# Display_port.net
KiCad netlist of a schematic drawn in Altium Designer
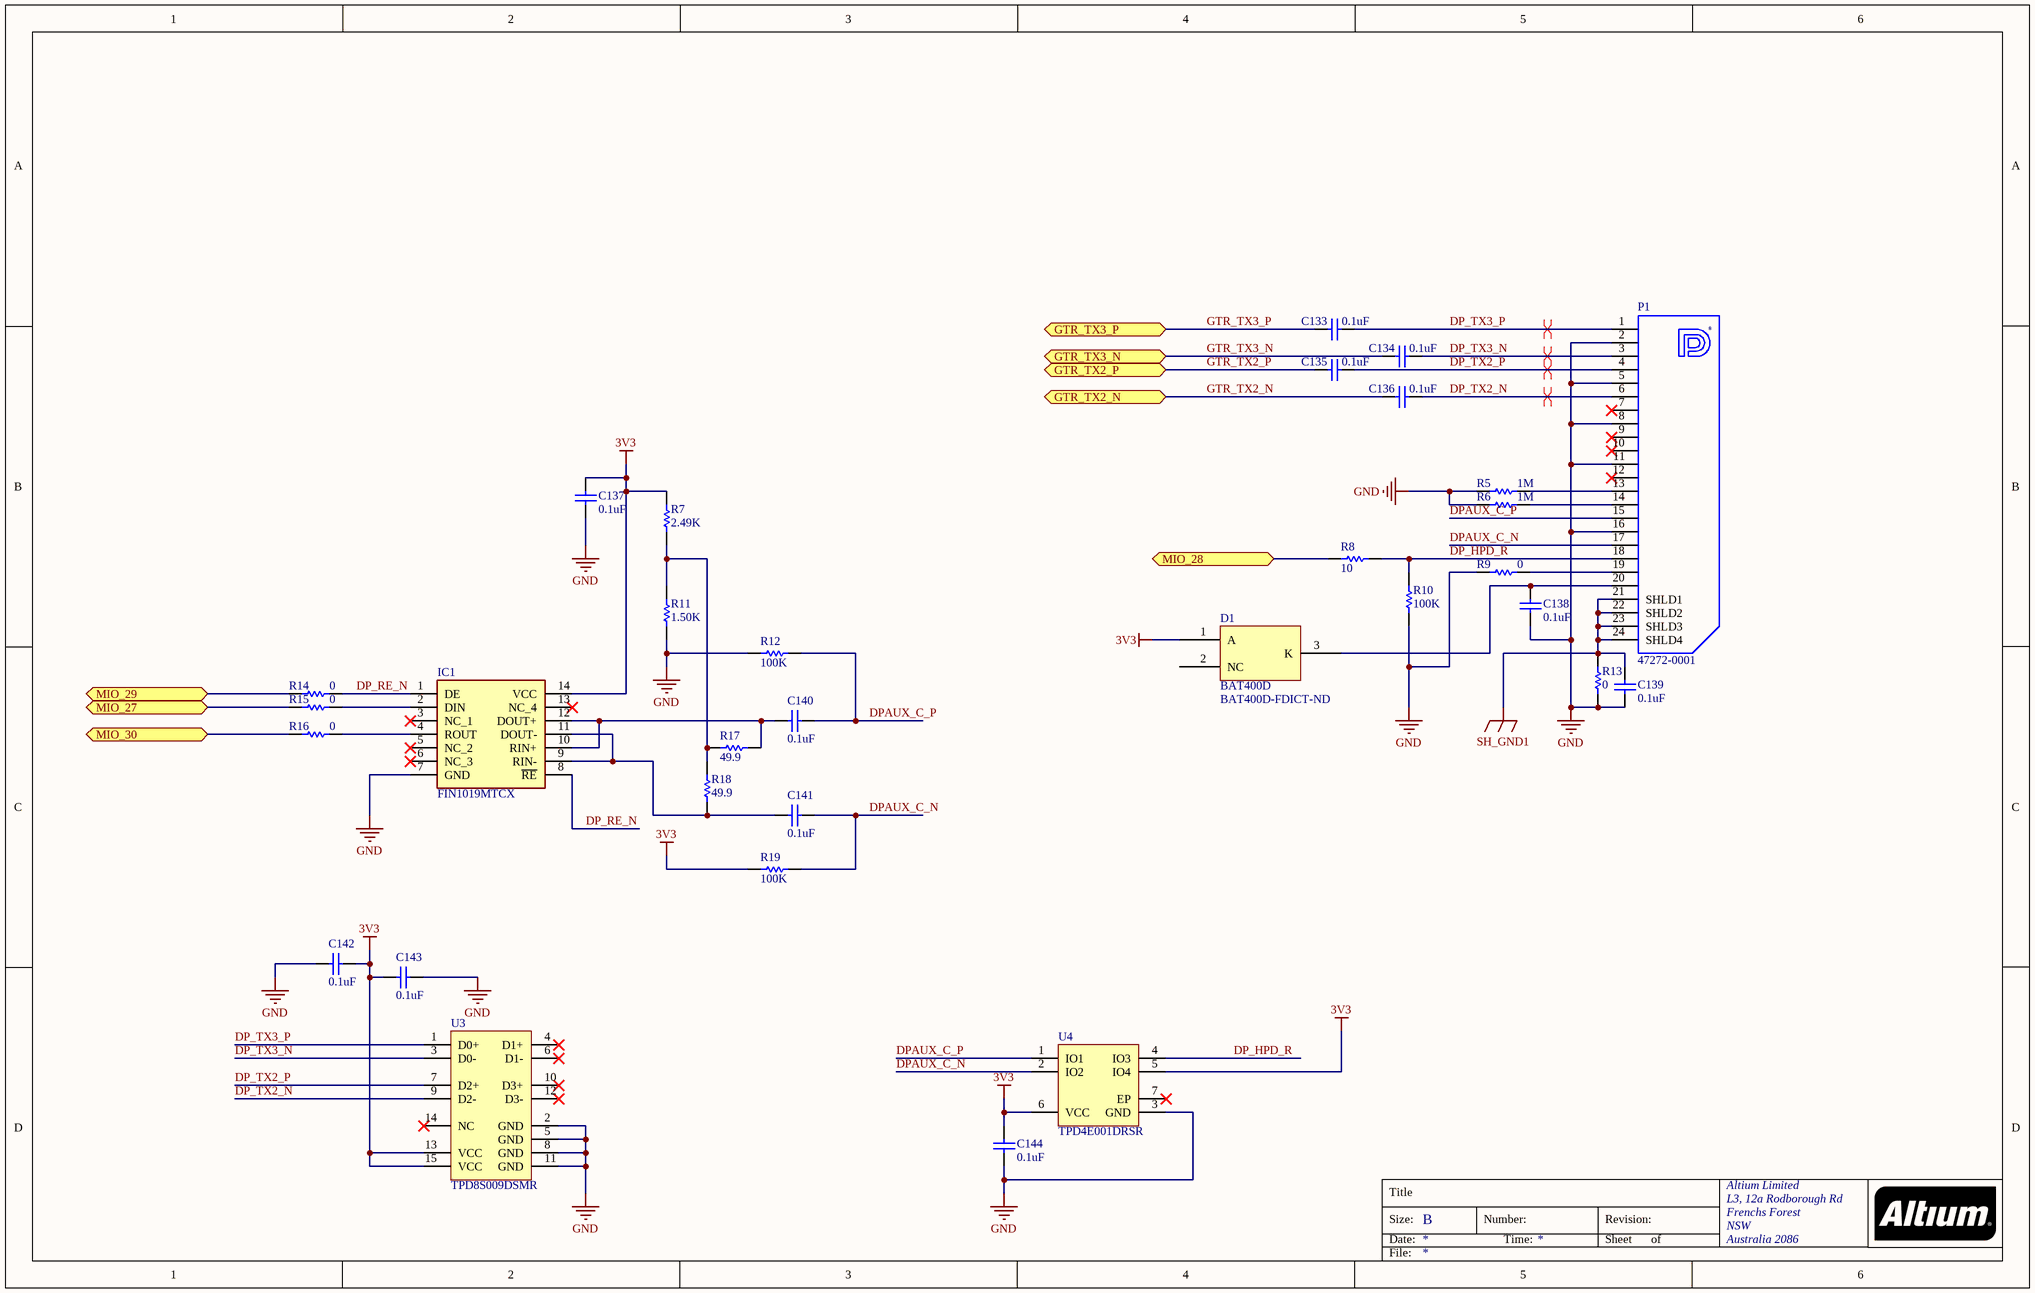
[diagram p0: Display_port.SchDoc]

(export (version "E")
  (design (tool "Eeschema 10.0.6"))
  (components
    (comp (ref "C133")
      (value "0.1uF")
      (footprint "CAPC0201(0603)33_N")
      (libsource (lib "my_schsymbols") (part "CAP_0201"))
    )
    (comp (ref "C134")
      (value "0.1uF")
      (footprint "CAPC0201(0603)33_N")
      (libsource (lib "my_schsymbols") (part "CAP_0201"))
    )
    (comp (ref "C135")
      (value "0.1uF")
      (footprint "CAPC0201(0603)33_N")
      (libsource (lib "my_schsymbols") (part "CAP_0201"))
    )
    (comp (ref "C136")
      (value "0.1uF")
      (footprint "CAPC0201(0603)33_N")
      (libsource (lib "my_schsymbols") (part "CAP_0201"))
    )
    (comp (ref "C137")
      (value "0.1uF")
      (footprint "CAPC0201(0603)33_N")
      (libsource (lib "my_schsymbols") (part "CAP_0201"))
    )
    (comp (ref "C138")
      (value "0.1uF")
      (footprint "CAPC0201(0603)33_N")
      (libsource (lib "my_schsymbols") (part "CAP_0201"))
    )
    (comp (ref "C139")
      (value "0.1uF")
      (footprint "CAPC0201(0603)33_N")
      (libsource (lib "my_schsymbols") (part "CAP_0201"))
    )
    (comp (ref "C140")
      (value "0.1uF")
      (footprint "CAPC0201(0603)33_N")
      (libsource (lib "my_schsymbols") (part "CAP_0201"))
    )
    (comp (ref "C141")
      (value "0.1uF")
      (footprint "CAPC0201(0603)33_N")
      (libsource (lib "my_schsymbols") (part "CAP_0201"))
    )
    (comp (ref "C142")
      (value "0.1uF")
      (footprint "CAPC0201(0603)33_N")
      (libsource (lib "my_schsymbols") (part "CAP_0201"))
    )
    (comp (ref "C143")
      (value "0.1uF")
      (footprint "CAPC0201(0603)33_N")
      (libsource (lib "my_schsymbols") (part "CAP_0201"))
    )
    (comp (ref "C144")
      (value "0.1uF")
      (footprint "CAPC0201(0603)33_N")
      (libsource (lib "my_schsymbols") (part "CAP_0201"))
    )
    (comp (ref "D1")
      (value "BAT400D")
      (footprint "SOT95P236X110-3N")
      (fields (field (name "SUPPLIER PART NUMBER 1") "BAT400D-FDICT-ND"))
      (libsource (lib "CGRA_schlib") (part "BAT400D"))
    )
    (comp (ref "IC1")
      (value "FIN1019MTCX")
      (footprint "SamacSys:SOP65P640X120-14N")
      (description "Integrated Circuit")
      (fields
        (field (name "MOUSER PART NUMBER") "512-FIN1019MTCX")
        (field (name "RS PART NUMBER") "8070805P")
      )
      (libsource (lib "*") (part "FIN1019MTCX"))
    )
    (comp (ref "P1")
      (value "47272-0001")
      (footprint "MOLX-47272-0001_V")
      (fields (field (name "MANUFACTURER") "Molex"))
      (libsource (lib "Altium Content Vault") (part "CN-1P-4M-DP20"))
    )
    (comp (ref "R5")
      (value "1M")
      (footprint "RESC0402(1005)_N")
      (libsource (lib "my_schsymbols") (part "RES_0402"))
    )
    (comp (ref "R6")
      (value "1M")
      (footprint "RESC0402(1005)_N")
      (libsource (lib "my_schsymbols") (part "RES_0402"))
    )
    (comp (ref "R7")
      (value "2.49K")
      (footprint "RESC0402(1005)_N")
      (libsource (lib "my_schsymbols") (part "RES_0402"))
    )
    (comp (ref "R8")
      (value "10")
      (footprint "RESC0402(1005)_N")
      (libsource (lib "my_schsymbols") (part "RES_0402"))
    )
    (comp (ref "R9")
      (value "0")
      (footprint "RESC0402(1005)_N")
      (libsource (lib "my_schsymbols") (part "RES_0402"))
    )
    (comp (ref "R10")
      (value "100K")
      (footprint "RESC0402(1005)_N")
      (libsource (lib "my_schsymbols") (part "RES_0402"))
    )
    (comp (ref "R11")
      (value "1.50K")
      (footprint "RESC0402(1005)_N")
      (libsource (lib "my_schsymbols") (part "RES_0402"))
    )
    (comp (ref "R12")
      (value "100K")
      (footprint "RESC0402(1005)_N")
      (libsource (lib "my_schsymbols") (part "RES_0402"))
    )
    (comp (ref "R13")
      (value "0")
      (footprint "RESC0402(1005)_N")
      (libsource (lib "my_schsymbols") (part "RES_0402"))
    )
    (comp (ref "R14")
      (value "0")
      (footprint "RESC0402(1005)_N")
      (libsource (lib "my_schsymbols") (part "RES_0402"))
    )
    (comp (ref "R15")
      (value "0")
      (footprint "RESC0402(1005)_N")
      (libsource (lib "my_schsymbols") (part "RES_0402"))
    )
    (comp (ref "R16")
      (value "0")
      (footprint "RESC0402(1005)_N")
      (libsource (lib "my_schsymbols") (part "RES_0402"))
    )
    (comp (ref "R17")
      (value "49.9")
      (footprint "RESC0402(1005)_N")
      (libsource (lib "my_schsymbols") (part "RES_0402"))
    )
    (comp (ref "R18")
      (value "49.9")
      (footprint "RESC0402(1005)_N")
      (libsource (lib "my_schsymbols") (part "RES_0402"))
    )
    (comp (ref "R19")
      (value "100K")
      (footprint "RESC0402(1005)_N")
      (libsource (lib "my_schsymbols") (part "RES_0402"))
    )
    (comp (ref "U3")
      (value "TPD8S009DSMR")
      (footprint "DSM0015A_V")
      (description "ESD Solution for HDMI / DisplayPort, 8 Channels, -40 to +85 degC, 15-pin SON (DSM)")
      (fields (field (name "MANUFACTURER") "Texas Instruments"))
      (libsource (lib "Altium Content Vault") (part "TI-TPD8S009-SON_DSM-15"))
    )
    (comp (ref "U4")
      (value "TPD4E001DRSR")
      (footprint "DRS0006A_V")
      (fields (field (name "MANUFACTURER") "Texas Instruments"))
      (libsource (lib "Altium Content Vault") (part "TI-TPD4E001-SON_DRS-6"))
    )
  )
  (nets
    (net (code "1") (name "/DPAUX_C_N") (class "Default")
      (node (ref "C141") (pin "2") (pinfunction "2_2") (pintype "passive"))
      (node (ref "P1") (pin "17") (pinfunction "17_17") (pintype "passive"))
      (node (ref "R19") (pin "1") (pinfunction "1_1") (pintype "passive"))
      (node (ref "U4") (pin "2") (pinfunction "IO2_2") (pintype "passive"))
    )
    (net (code "2") (name "/DPAUX_C_P") (class "Default")
      (node (ref "C140") (pin "2") (pinfunction "2_2") (pintype "passive"))
      (node (ref "P1") (pin "15") (pinfunction "15_15") (pintype "passive"))
      (node (ref "R12") (pin "1") (pinfunction "1_1") (pintype "passive"))
      (node (ref "U4") (pin "1") (pinfunction "IO1_1") (pintype "passive"))
    )
    (net (code "3") (name "/DP_HPD_R") (class "Default")
      (node (ref "P1") (pin "18") (pinfunction "18_18") (pintype "passive"))
      (node (ref "R10") (pin "2") (pinfunction "2_2") (pintype "passive"))
      (node (ref "R8") (pin "2") (pinfunction "2_2") (pintype "passive"))
      (node (ref "U4") (pin "4") (pinfunction "IO3_4") (pintype "passive"))
    )
    (net (code "4") (name "/DP_RE_N") (class "Default")
      (node (ref "IC1") (pin "1") (pinfunction "DE_1") (pintype "passive"))
      (node (ref "IC1") (pin "8") (pinfunction "~{RE}_8") (pintype "passive"))
      (node (ref "R14") (pin "1") (pinfunction "1_1") (pintype "passive"))
    )
    (net (code "5") (name "/DP_TX2_N") (class "Default")
      (node (ref "C136") (pin "2") (pinfunction "2_2") (pintype "passive"))
      (node (ref "P1") (pin "6") (pinfunction "6_6") (pintype "passive"))
      (node (ref "U3") (pin "9") (pinfunction "D2-_9") (pintype "passive"))
    )
    (net (code "6") (name "/DP_TX2_P") (class "Default")
      (node (ref "C135") (pin "2") (pinfunction "2_2") (pintype "passive"))
      (node (ref "P1") (pin "4") (pinfunction "4_4") (pintype "passive"))
      (node (ref "U3") (pin "7") (pinfunction "D2+_7") (pintype "passive"))
    )
    (net (code "7") (name "/DP_TX3_N") (class "Default")
      (node (ref "C134") (pin "2") (pinfunction "2_2") (pintype "passive"))
      (node (ref "P1") (pin "3") (pinfunction "3_3") (pintype "passive"))
      (node (ref "U3") (pin "3") (pinfunction "D0-_3") (pintype "passive"))
    )
    (net (code "8") (name "/DP_TX3_P") (class "Default")
      (node (ref "C133") (pin "2") (pinfunction "2_2") (pintype "passive"))
      (node (ref "P1") (pin "1") (pinfunction "1_1") (pintype "passive"))
      (node (ref "U3") (pin "1") (pinfunction "D0+_1") (pintype "passive"))
    )
    (net (code "9") (name "/GTR_TX2_N") (class "Default")
      (node (ref "C136") (pin "1") (pinfunction "1_1") (pintype "passive"))
    )
    (net (code "10") (name "/GTR_TX2_P") (class "Default")
      (node (ref "C135") (pin "1") (pinfunction "1_1") (pintype "passive"))
    )
    (net (code "11") (name "/GTR_TX3_N") (class "Default")
      (node (ref "C134") (pin "1") (pinfunction "1_1") (pintype "passive"))
    )
    (net (code "12") (name "/GTR_TX3_P") (class "Default")
      (node (ref "C133") (pin "1") (pinfunction "1_1") (pintype "passive"))
    )
    (net (code "13") (name "/MIO_27") (class "Default")
      (node (ref "R15") (pin "2") (pinfunction "2_2") (pintype "passive"))
    )
    (net (code "14") (name "/MIO_28") (class "Default")
      (node (ref "R8") (pin "1") (pinfunction "1_1") (pintype "passive"))
    )
    (net (code "15") (name "/MIO_29") (class "Default")
      (node (ref "R14") (pin "2") (pinfunction "2_2") (pintype "passive"))
    )
    (net (code "16") (name "/MIO_30") (class "Default")
      (node (ref "R16") (pin "2") (pinfunction "2_2") (pintype "passive"))
    )
    (net (code "17") (name "3V3") (class "Default")
      (node (ref "C137") (pin "2") (pinfunction "2_2") (pintype "passive"))
      (node (ref "C142") (pin "1") (pinfunction "1_1") (pintype "passive"))
      (node (ref "C143") (pin "2") (pinfunction "2_2") (pintype "passive"))
      (node (ref "C144") (pin "2") (pinfunction "2_2") (pintype "passive"))
      (node (ref "D1") (pin "1") (pinfunction "A_1") (pintype "passive"))
      (node (ref "IC1") (pin "14") (pinfunction "VCC_14") (pintype "passive"))
      (node (ref "R19") (pin "2") (pinfunction "2_2") (pintype "passive"))
      (node (ref "R7") (pin "2") (pinfunction "2_2") (pintype "passive"))
      (node (ref "U3") (pin "13") (pinfunction "VCC_13") (pintype "power_in"))
      (node (ref "U3") (pin "15") (pinfunction "VCC_15") (pintype "power_in"))
      (node (ref "U4") (pin "5") (pinfunction "IO4_5") (pintype "passive"))
      (node (ref "U4") (pin "6") (pinfunction "VCC_6") (pintype "power_in"))
    )
    (net (code "18") (name "GND") (class "Default")
      (node (ref "C137") (pin "1") (pinfunction "1_1") (pintype "passive"))
      (node (ref "C138") (pin "1") (pinfunction "1_1") (pintype "passive"))
      (node (ref "C139") (pin "1") (pinfunction "1_1") (pintype "passive"))
      (node (ref "C142") (pin "2") (pinfunction "2_2") (pintype "passive"))
      (node (ref "C143") (pin "1") (pinfunction "1_1") (pintype "passive"))
      (node (ref "C144") (pin "1") (pinfunction "1_1") (pintype "passive"))
      (node (ref "IC1") (pin "7") (pinfunction "GND_7") (pintype "passive"))
      (node (ref "P1") (pin "11") (pinfunction "11_11") (pintype "passive"))
      (node (ref "P1") (pin "16") (pinfunction "16_16") (pintype "passive"))
      (node (ref "P1") (pin "2") (pinfunction "2_2") (pintype "passive"))
      (node (ref "P1") (pin "5") (pinfunction "5_5") (pintype "passive"))
      (node (ref "P1") (pin "8") (pinfunction "8_8") (pintype "passive"))
      (node (ref "R10") (pin "1") (pinfunction "1_1") (pintype "passive"))
      (node (ref "R11") (pin "1") (pinfunction "1_1") (pintype "passive"))
      (node (ref "R12") (pin "2") (pinfunction "2_2") (pintype "passive"))
      (node (ref "R13") (pin "2") (pinfunction "2_2") (pintype "passive"))
      (node (ref "R5") (pin "1") (pinfunction "1_1") (pintype "passive"))
      (node (ref "R6") (pin "1") (pinfunction "1_1") (pintype "passive"))
      (node (ref "R9") (pin "1") (pinfunction "1_1") (pintype "passive"))
      (node (ref "U3") (pin "11") (pinfunction "GND_11") (pintype "power_in"))
      (node (ref "U3") (pin "2") (pinfunction "GND_2") (pintype "power_in"))
      (node (ref "U3") (pin "5") (pinfunction "GND_5") (pintype "power_in"))
      (node (ref "U3") (pin "8") (pinfunction "GND_8") (pintype "power_in"))
      (node (ref "U4") (pin "3") (pinfunction "GND_3") (pintype "power_in"))
    )
    (net (code "19") (name "Net-(D1-K)") (class "Default")
      (node (ref "C138") (pin "2") (pinfunction "2_2") (pintype "passive"))
      (node (ref "D1") (pin "3") (pinfunction "K_3") (pintype "passive"))
      (node (ref "P1") (pin "20") (pinfunction "20_20") (pintype "passive"))
    )
    (net (code "20") (name "Net-(IC1-DIN)") (class "Default")
      (node (ref "IC1") (pin "2") (pinfunction "DIN_2") (pintype "passive"))
      (node (ref "R15") (pin "1") (pinfunction "1_1") (pintype "passive"))
    )
    (net (code "21") (name "Net-(IC1-DOUT+)") (class "Default")
      (node (ref "C140") (pin "1") (pinfunction "1_1") (pintype "passive"))
      (node (ref "IC1") (pin "10") (pinfunction "RIN+_10") (pintype "passive"))
      (node (ref "IC1") (pin "12") (pinfunction "DOUT+_12") (pintype "passive"))
      (node (ref "R17") (pin "1") (pinfunction "1_1") (pintype "passive"))
    )
    (net (code "22") (name "Net-(IC1-DOUT-)") (class "Default")
      (node (ref "C141") (pin "1") (pinfunction "1_1") (pintype "passive"))
      (node (ref "IC1") (pin "11") (pinfunction "DOUT-_11") (pintype "passive"))
      (node (ref "IC1") (pin "9") (pinfunction "RIN-_9") (pintype "passive"))
      (node (ref "R18") (pin "2") (pinfunction "2_2") (pintype "passive"))
    )
    (net (code "23") (name "Net-(IC1-ROUT)") (class "Default")
      (node (ref "IC1") (pin "4") (pinfunction "ROUT_4") (pintype "passive"))
      (node (ref "R16") (pin "1") (pinfunction "1_1") (pintype "passive"))
    )
    (net (code "24") (name "Net-(P1-Pad13)") (class "Default")
      (node (ref "P1") (pin "13") (pinfunction "13_13") (pintype "passive"))
      (node (ref "R5") (pin "2") (pinfunction "2_2") (pintype "passive"))
    )
    (net (code "25") (name "Net-(P1-Pad14)") (class "Default")
      (node (ref "P1") (pin "14") (pinfunction "14_14") (pintype "passive"))
      (node (ref "R6") (pin "2") (pinfunction "2_2") (pintype "passive"))
    )
    (net (code "26") (name "Net-(P1-Pad19)") (class "Default")
      (node (ref "P1") (pin "19") (pinfunction "19_19") (pintype "passive"))
      (node (ref "R9") (pin "2") (pinfunction "2_2") (pintype "passive"))
    )
    (net (code "27") (name "Net-(R11-Pad2)") (class "Default")
      (node (ref "R11") (pin "2") (pinfunction "2_2") (pintype "passive"))
      (node (ref "R17") (pin "2") (pinfunction "2_2") (pintype "passive"))
      (node (ref "R18") (pin "1") (pinfunction "1_1") (pintype "passive"))
      (node (ref "R7") (pin "1") (pinfunction "1_1") (pintype "passive"))
    )
    (net (code "28") (name "SH_GND1") (class "Default")
      (node (ref "C139") (pin "2") (pinfunction "2_2") (pintype "passive"))
      (node (ref "P1") (pin "21") (pinfunction "SHLD1_21") (pintype "passive"))
      (node (ref "P1") (pin "22") (pinfunction "SHLD2_22") (pintype "passive"))
      (node (ref "P1") (pin "23") (pinfunction "SHLD3_23") (pintype "passive"))
      (node (ref "P1") (pin "24") (pinfunction "SHLD4_24") (pintype "passive"))
      (node (ref "R13") (pin "1") (pinfunction "1_1") (pintype "passive"))
    )
    (net (code "29") (name "unconnected-(D1-NC-Pad2)") (class "Default")
      (node (ref "D1") (pin "2") (pinfunction "NC_2") (pintype "passive"))
    )
    (net (code "30") (name "unconnected-(IC1-NC_1-Pad3)") (class "Default")
      (node (ref "IC1") (pin "3") (pinfunction "NC_1_3") (pintype "passive+no_connect"))
    )
    (net (code "31") (name "unconnected-(IC1-NC_2-Pad5)") (class "Default")
      (node (ref "IC1") (pin "5") (pinfunction "NC_2_5") (pintype "passive+no_connect"))
    )
    (net (code "32") (name "unconnected-(IC1-NC_3-Pad6)") (class "Default")
      (node (ref "IC1") (pin "6") (pinfunction "NC_3_6") (pintype "passive+no_connect"))
    )
    (net (code "33") (name "unconnected-(IC1-NC_4-Pad13)") (class "Default")
      (node (ref "IC1") (pin "13") (pinfunction "NC_4_13") (pintype "passive+no_connect"))
    )
    (net (code "34") (name "unconnected-(P1-Pad7)") (class "Default")
      (node (ref "P1") (pin "7") (pinfunction "7_7") (pintype "passive+no_connect"))
    )
    (net (code "35") (name "unconnected-(P1-Pad9)") (class "Default")
      (node (ref "P1") (pin "9") (pinfunction "9_9") (pintype "passive+no_connect"))
    )
    (net (code "36") (name "unconnected-(P1-Pad10)") (class "Default")
      (node (ref "P1") (pin "10") (pinfunction "10_10") (pintype "passive+no_connect"))
    )
    (net (code "37") (name "unconnected-(P1-Pad12)") (class "Default")
      (node (ref "P1") (pin "12") (pinfunction "12_12") (pintype "passive+no_connect"))
    )
    (net (code "38") (name "unconnected-(U3-D1+-Pad4)") (class "Default")
      (node (ref "U3") (pin "4") (pinfunction "D1+_4") (pintype "passive+no_connect"))
    )
    (net (code "39") (name "unconnected-(U3-D1--Pad6)") (class "Default")
      (node (ref "U3") (pin "6") (pinfunction "D1-_6") (pintype "passive+no_connect"))
    )
    (net (code "40") (name "unconnected-(U3-D3+-Pad10)") (class "Default")
      (node (ref "U3") (pin "10") (pinfunction "D3+_10") (pintype "passive+no_connect"))
    )
    (net (code "41") (name "unconnected-(U3-D3--Pad12)") (class "Default")
      (node (ref "U3") (pin "12") (pinfunction "D3-_12") (pintype "passive+no_connect"))
    )
    (net (code "42") (name "unconnected-(U3-NC-Pad14)") (class "Default")
      (node (ref "U3") (pin "14") (pinfunction "NC_14") (pintype "passive+no_connect"))
    )
    (net (code "43") (name "unconnected-(U4-EP-Pad7)") (class "Default")
      (node (ref "U4") (pin "7") (pinfunction "EP_7") (pintype "power_in+no_connect"))
    )
  )
)
